# PMOS.net
KiCad netlist of a schematic drawn in Altium Designer
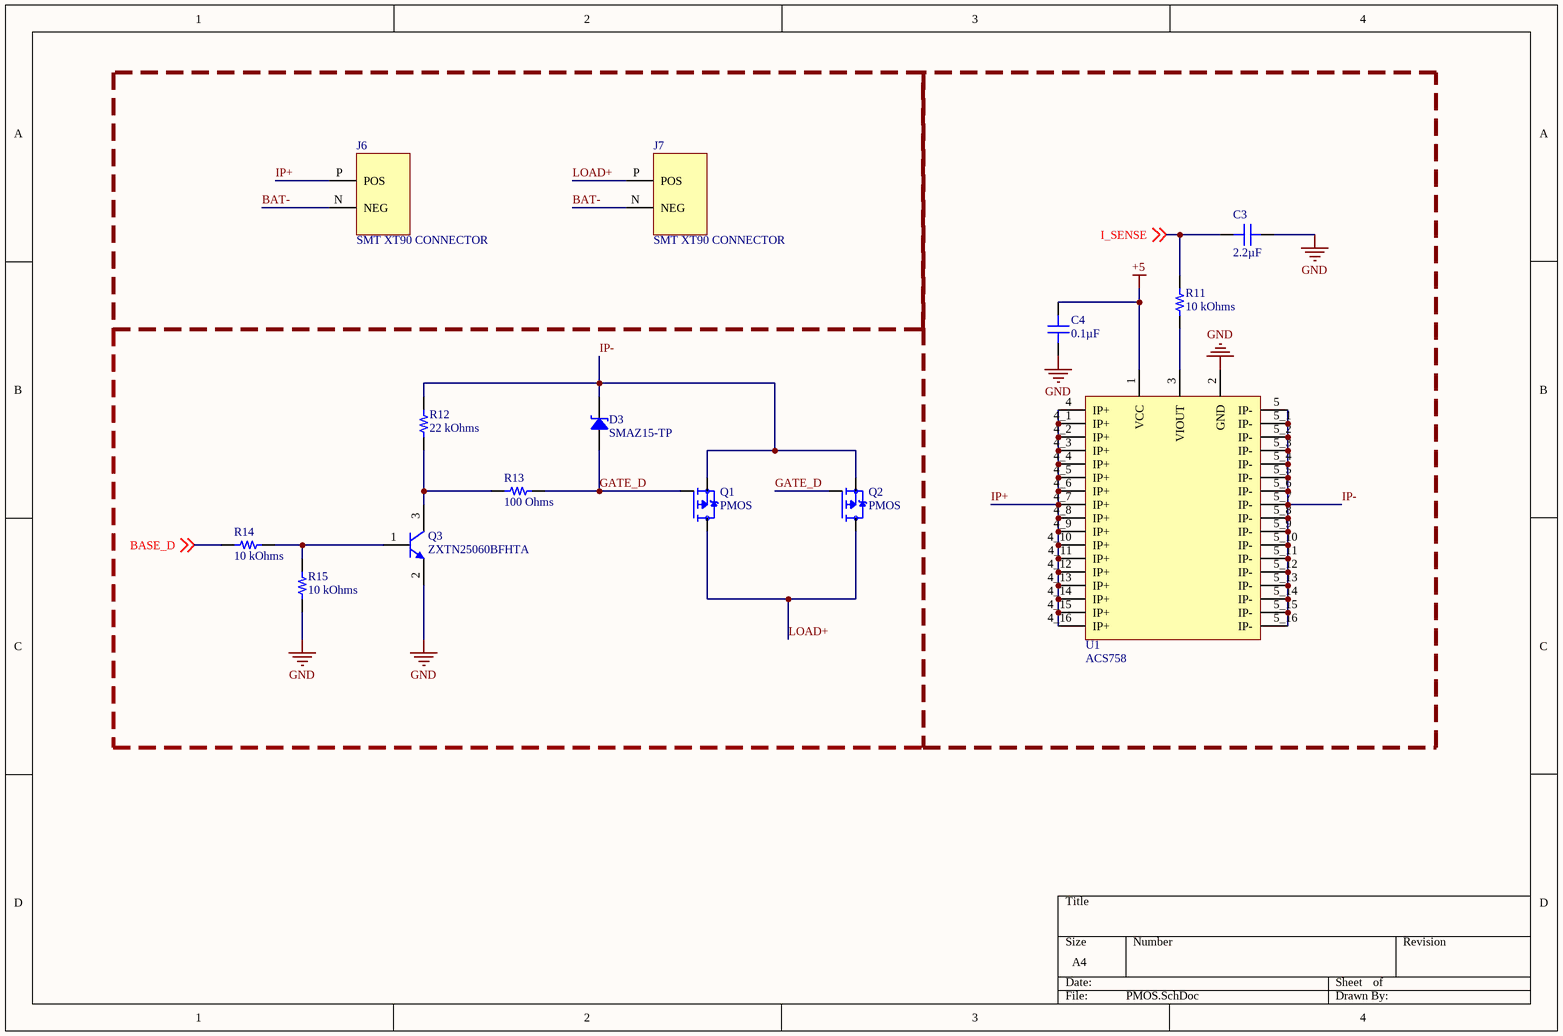
[diagram p0: PMOS.SchDoc]

(export (version "E")
  (design (tool "Eeschema 10.0.6"))
  (components
    (comp (ref "C3")
      (value "2.2µF")
      (footprint "CAP 0603_1608")
      (description "CAP CER 2.2UF 16V X5R 0603")
      (fields
        (field (name "PART NUMBER") "0603YD225KAT4A")
        (field (name "CAPACITANCE") "2.2µF")
        (field (name "MANUFACTURER") "AVX Corporation")
      )
      (libsource (lib "Celestial Altium Library - altium_library (1)") (part "Capacitor"))
    )
    (comp (ref "C4")
      (value "0.1µF")
      (footprint "CAP 0603_1608")
      (description "CAP CER 0.1UF 50V Y5V 0603")
      (fields
        (field (name "PART NUMBER") "06035G104ZAT2A")
        (field (name "CAPACITANCE") "0.1µF")
        (field (name "MANUFACTURER") "AVX Corporation")
      )
      (libsource (lib "Celestial Altium Library - altium_library (1)") (part "Capacitor"))
    )
    (comp (ref "D3")
      (value "SMAZ15-TP")
      (footprint "DO214AC SMA")
      (description "DIODE ZENER 15V 1W DO214AC")
      (fields (field (name "MANUFACTURER") "Micro Commercial Co") (field (name "TOLERANCE") "±5%"))
      (libsource (lib "Celestial Altium Library - altium_library (1)") (part "Diode Zener"))
    )
    (comp (ref "J6")
      (value "SMT XT90 CONNECTOR")
      (footprint "XT90_PW-M")
      (fields (field (name "JLCPCB PART NUMBER") "C3040689"))
      (libsource (lib "altiumlive") (part "XT90_PW-M"))
    )
    (comp (ref "J7")
      (value "SMT XT90 CONNECTOR")
      (footprint "XT90_PW-M")
      (fields (field (name "JLCPCB PART NUMBER") "C3040689"))
      (libsource (lib "altiumlive") (part "XT90_PW-M"))
    )
    (comp (ref "Q1")
      (value "PMOS")
      (footprint "TO-263-3-2")
      (fields (field (name "JLCPCB PART NUMBER") "C2909634"))
      (libsource (lib "altiumlive") (part "PMOS"))
    )
    (comp (ref "Q2")
      (value "PMOS")
      (footprint "TO-263-3-2")
      (fields (field (name "JLCPCB PART NUMBER") "C2909634"))
      (libsource (lib "altiumlive") (part "PMOS"))
    )
    (comp (ref "Q3")
      (value "ZXTN25060BFHTA")
      (footprint "DIODES SOT-23-3")
      (description "TRANS NPN 60V 3.5A SOT23-3")
      (fields (field (name "MANUFACTURER") "Diodes Incorporated") (field (name "JLCPCB PART NUMBER") "C2145"))
      (libsource (lib "Celestial Altium Library - altium_library (1)") (part "DIODES INC NPN SOT-23-3"))
    )
    (comp (ref "R11")
      (value "10 kOhms")
      (footprint "RES 0603_1608")
      (description "RES SMD 10K OHM 0.1% 1/16W 0603")
      (fields
        (field (name "PART NUMBER") "CPF0603B10KE")
        (field (name "MANUFACTURER") "TE Connectivity Passive Product")
      )
      (libsource (lib "Celestial Altium Library - altium_library (1)") (part "Resistor"))
    )
    (comp (ref "R12")
      (value "22 kOhms")
      (footprint "YAGEO RES 1206_3216")
      (description "RES SMD 22K OHM 0.1% 1/4W 1206")
      (fields (field (name "PART NUMBER") "RT1206BRD0722KL") (field (name "MANUFACTURER") "Yageo"))
      (libsource (lib "Celestial Altium Library - altium_library (1)") (part "Resistor"))
    )
    (comp (ref "R13")
      (value "100 Ohms")
      (footprint "RES 1206_3216")
      (description "RES 100 OHM 1% 1/2W 1206")
      (fields
        (field (name "PART NUMBER") "RNCP1206FTD100R")
        (field (name "MANUFACTURER") "Stackpole Electronics Inc")
      )
      (libsource (lib "Celestial Altium Library - altium_library (1)") (part "Resistor"))
    )
    (comp (ref "R14")
      (value "10 kOhms")
      (footprint "RES 0805_2012")
      (description "RES SMD 10K OHM 0.01% 1/5W 0805")
      (fields
        (field (name "PART NUMBER") "Y162410K0000T9R")
        (field (name "MANUFACTURER") "Vishay Foil Resistors (Division of Vishay Precision Group)")
      )
      (libsource (lib "Celestial Altium Library - altium_library (1)") (part "Resistor"))
    )
    (comp (ref "R15")
      (value "10 kOhms")
      (footprint "RES 0805_2012")
      (description "RES SMD 10K OHM 0.01% 1/5W 0805")
      (fields
        (field (name "PART NUMBER") "Y162410K0000T9R")
        (field (name "MANUFACTURER") "Vishay Foil Resistors (Division of Vishay Precision Group)")
      )
      (libsource (lib "Celestial Altium Library - altium_library (1)") (part "Resistor"))
    )
    (comp (ref "U1")
      (value "ACS758")
      (footprint "ACS758")
      (description "Current Sensor 150A 1 Channel Hall Effect, Open Loop Unidirectional 5-CB Formed Leads, PFF")
      (libsource (lib "altiumlive") (part "ACS758"))
    )
  )
  (nets
    (net (code "1") (name "+5") (class "Default")
      (node (ref "C4") (pin "2") (pinfunction "2_2") (pintype "passive"))
      (node (ref "U1") (pin "1") (pinfunction "VCC_1") (pintype "power_in"))
    )
    (net (code "2") (name "/BAT-") (class "Default")
      (node (ref "J6") (pin "N") (pinfunction "NEG_N") (pintype "passive"))
      (node (ref "J7") (pin "N") (pinfunction "NEG_N") (pintype "passive"))
    )
    (net (code "3") (name "/GATE_D") (class "Default")
      (node (ref "D3") (pin "1") (pinfunction "1_1") (pintype "passive"))
      (node (ref "Q1") (pin "1") (pinfunction "G_1") (pintype "passive"))
      (node (ref "Q2") (pin "1") (pinfunction "G_1") (pintype "passive"))
      (node (ref "R13") (pin "2") (pinfunction "2_2") (pintype "passive"))
    )
    (net (code "4") (name "/IP+") (class "Default")
      (node (ref "J6") (pin "P") (pinfunction "POS_P") (pintype "passive"))
      (node (ref "U1") (pin "4") (pinfunction "IP+_4") (pintype "power_in"))
      (node (ref "U1") (pin "4_1") (pinfunction "IP+_4_1") (pintype "power_in"))
      (node (ref "U1") (pin "4_10") (pinfunction "IP+_4_10") (pintype "power_in"))
      (node (ref "U1") (pin "4_11") (pinfunction "IP+_4_11") (pintype "power_in"))
      (node (ref "U1") (pin "4_12") (pinfunction "IP+_4_12") (pintype "power_in"))
      (node (ref "U1") (pin "4_13") (pinfunction "IP+_4_13") (pintype "power_in"))
      (node (ref "U1") (pin "4_14") (pinfunction "IP+_4_14") (pintype "power_in"))
      (node (ref "U1") (pin "4_15") (pinfunction "IP+_4_15") (pintype "power_in"))
      (node (ref "U1") (pin "4_16") (pinfunction "IP+_4_16") (pintype "power_in"))
      (node (ref "U1") (pin "4_2") (pinfunction "IP+_4_2") (pintype "power_in"))
      (node (ref "U1") (pin "4_3") (pinfunction "IP+_4_3") (pintype "power_in"))
      (node (ref "U1") (pin "4_4") (pinfunction "IP+_4_4") (pintype "power_in"))
      (node (ref "U1") (pin "4_5") (pinfunction "IP+_4_5") (pintype "power_in"))
      (node (ref "U1") (pin "4_6") (pinfunction "IP+_4_6") (pintype "power_in"))
      (node (ref "U1") (pin "4_7") (pinfunction "IP+_4_7") (pintype "power_in"))
      (node (ref "U1") (pin "4_8") (pinfunction "IP+_4_8") (pintype "power_in"))
      (node (ref "U1") (pin "4_9") (pinfunction "IP+_4_9") (pintype "power_in"))
    )
    (net (code "5") (name "/IP-") (class "Default")
      (node (ref "D3") (pin "2") (pinfunction "2_2") (pintype "passive"))
      (node (ref "Q1") (pin "2") (pinfunction "S_2") (pintype "passive"))
      (node (ref "Q2") (pin "2") (pinfunction "S_2") (pintype "passive"))
      (node (ref "R12") (pin "2") (pinfunction "2_2") (pintype "passive"))
      (node (ref "U1") (pin "5") (pinfunction "IP-_5") (pintype "power_in"))
      (node (ref "U1") (pin "5_1") (pinfunction "IP-_5_1") (pintype "power_in"))
      (node (ref "U1") (pin "5_10") (pinfunction "IP-_5_10") (pintype "power_in"))
      (node (ref "U1") (pin "5_11") (pinfunction "IP-_5_11") (pintype "power_in"))
      (node (ref "U1") (pin "5_12") (pinfunction "IP-_5_12") (pintype "power_in"))
      (node (ref "U1") (pin "5_13") (pinfunction "IP-_5_13") (pintype "power_in"))
      (node (ref "U1") (pin "5_14") (pinfunction "IP-_5_14") (pintype "power_in"))
      (node (ref "U1") (pin "5_15") (pinfunction "IP-_5_15") (pintype "power_in"))
      (node (ref "U1") (pin "5_16") (pinfunction "IP-_5_16") (pintype "power_in"))
      (node (ref "U1") (pin "5_2") (pinfunction "IP-_5_2") (pintype "power_in"))
      (node (ref "U1") (pin "5_3") (pinfunction "IP-_5_3") (pintype "power_in"))
      (node (ref "U1") (pin "5_4") (pinfunction "IP-_5_4") (pintype "power_in"))
      (node (ref "U1") (pin "5_5") (pinfunction "IP-_5_5") (pintype "power_in"))
      (node (ref "U1") (pin "5_6") (pinfunction "IP-_5_6") (pintype "power_in"))
      (node (ref "U1") (pin "5_7") (pinfunction "IP-_5_7") (pintype "power_in"))
      (node (ref "U1") (pin "5_8") (pinfunction "IP-_5_8") (pintype "power_in"))
      (node (ref "U1") (pin "5_9") (pinfunction "IP-_5_9") (pintype "power_in"))
    )
    (net (code "6") (name "/LOAD+") (class "Default")
      (node (ref "J7") (pin "P") (pinfunction "POS_P") (pintype "passive"))
      (node (ref "Q1") (pin "3") (pinfunction "D_3") (pintype "passive"))
      (node (ref "Q2") (pin "3") (pinfunction "D_3") (pintype "passive"))
    )
    (net (code "7") (name "BASE_D") (class "Default")
      (node (ref "R14") (pin "2") (pinfunction "2_2") (pintype "passive"))
    )
    (net (code "8") (name "GND") (class "Default")
      (node (ref "C3") (pin "2") (pinfunction "2_2") (pintype "passive"))
      (node (ref "C4") (pin "1") (pinfunction "1_1") (pintype "passive"))
      (node (ref "Q3") (pin "2") (pinfunction "E_2") (pintype "passive"))
      (node (ref "R15") (pin "1") (pinfunction "1_1") (pintype "passive"))
      (node (ref "U1") (pin "2") (pinfunction "GND_2") (pintype "power_in"))
    )
    (net (code "9") (name "I_SENSE") (class "Default")
      (node (ref "C3") (pin "1") (pinfunction "1_1") (pintype "passive"))
      (node (ref "R11") (pin "2") (pinfunction "2_2") (pintype "passive"))
    )
    (net (code "10") (name "Net-(Q3-B)") (class "Default")
      (node (ref "Q3") (pin "1") (pinfunction "B_1") (pintype "passive"))
      (node (ref "R14") (pin "1") (pinfunction "1_1") (pintype "passive"))
      (node (ref "R15") (pin "2") (pinfunction "2_2") (pintype "passive"))
    )
    (net (code "11") (name "Net-(Q3-C)") (class "Default")
      (node (ref "Q3") (pin "3") (pinfunction "C_3") (pintype "passive"))
      (node (ref "R12") (pin "1") (pinfunction "1_1") (pintype "passive"))
      (node (ref "R13") (pin "1") (pinfunction "1_1") (pintype "passive"))
    )
    (net (code "12") (name "Net-(U1-VIOUT)") (class "Default")
      (node (ref "R11") (pin "1") (pinfunction "1_1") (pintype "passive"))
      (node (ref "U1") (pin "3") (pinfunction "VIOUT_3") (pintype "passive"))
    )
  )
)
